# 04_MP_SIGNAL.net
KiCad netlist of a schematic drawn in Altium Designer
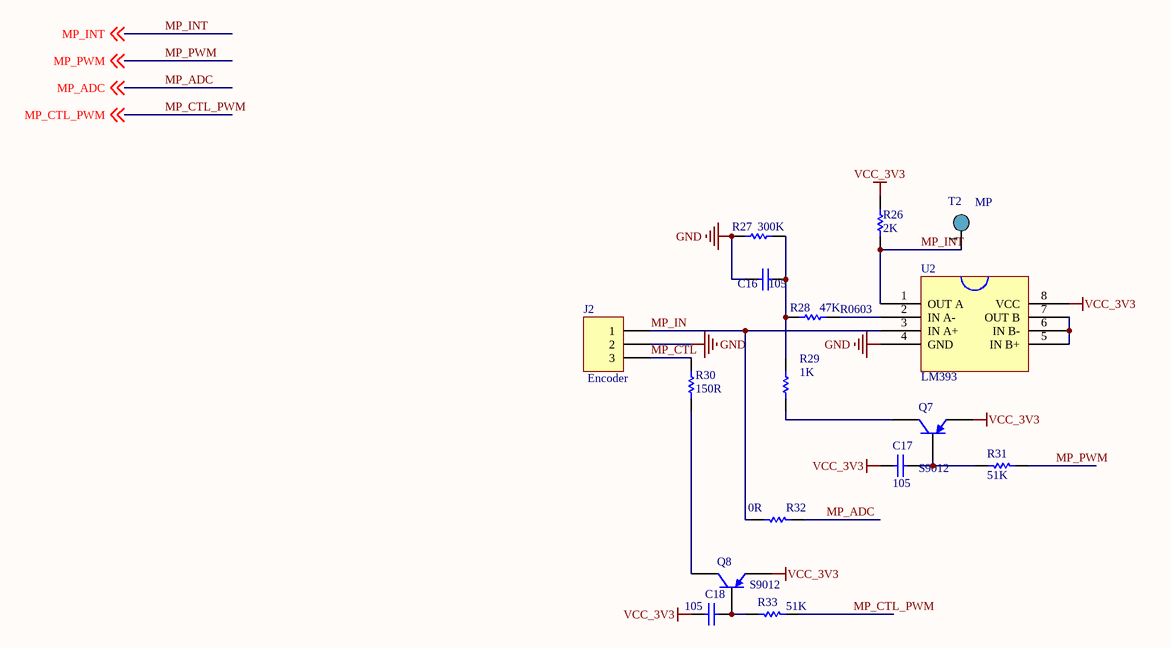
[diagram p0: 04 MP_SIGNAL.SchDoc]

(export (version "E")
  (design (tool "Eeschema 10.0.6"))
  (components
    (comp (ref "C16")
      (value "105")
      (footprint "R0603")
      (description "Capacitor")
      (fields
        (field (name "MANUFACTURER") "Generic Components")
        (field (name "PUBLISHER") "Altium Hobart Technology Centre")
      )
      (libsource (lib "") (part "Cap_1"))
    )
    (comp (ref "C17")
      (value "105")
      (footprint "C0603")
      (description "Capacitor")
      (fields
        (field (name "MANUFACTURER") "Generic Components")
        (field (name "PUBLISHER") "Altium Hobart Technology Centre")
      )
      (libsource (lib "") (part "Cap_1"))
    )
    (comp (ref "C18")
      (value "105")
      (footprint "C0603")
      (description "Capacitor")
      (fields
        (field (name "MANUFACTURER") "Generic Components")
        (field (name "PUBLISHER") "Altium Hobart Technology Centre")
      )
      (libsource (lib "Miscellaneous Devices") (part "Cap"))
    )
    (comp (ref "J2")
      (value "Encoder")
      (footprint "PH2.0*3")
      (description "Header, 3-Pin")
      (fields (field (name "MANUFACTURER") "Generic Components"))
      (libsource (lib "Miscellaneous Connectors") (part "Header 3"))
    )
    (comp (ref "Q7")
      (value "S9012")
      (footprint "PNP-SOT-23")
      (description "PNP General Purpose Amplifier")
      (fields (field (name "PUBLISHER") "Altium Limited"))
      (libsource (lib "Miscellaneous Devices") (part "2N3906"))
    )
    (comp (ref "Q8")
      (value "S9012")
      (footprint "PNP-SOT-23")
      (description "PNP General Purpose Amplifier")
      (fields (field (name "PUBLISHER") "Altium Limited"))
      (libsource (lib "Miscellaneous Devices") (part "2N3906"))
    )
    (comp (ref "R26")
      (value "2K")
      (footprint "R0603")
      (description "Resistor")
      (fields
        (field (name "MANUFACTURER") "Generic Components")
        (field (name "PUBLISHER") "Altium Hobart Technology Centre")
      )
      (libsource (lib "") (part "Res1_1"))
    )
    (comp (ref "R27")
      (value "300K")
      (footprint "R0603")
      (description "Resistor")
      (fields
        (field (name "MANUFACTURER") "Generic Components")
        (field (name "PUBLISHER") "Altium Hobart Technology Centre")
      )
      (libsource (lib "") (part "Res1_1"))
    )
    (comp (ref "R28")
      (value "47K")
      (footprint "R0603")
      (description "Resistor")
      (fields
        (field (name "MANUFACTURER") "Generic Components")
        (field (name "PUBLISHER") "Altium Hobart Technology Centre")
      )
      (libsource (lib "") (part "Res1_1"))
    )
    (comp (ref "R29")
      (value "1K")
      (footprint "R0603")
      (description "Resistor")
      (fields
        (field (name "MANUFACTURER") "Generic Components")
        (field (name "PUBLISHER") "Altium Hobart Technology Centre")
      )
      (libsource (lib "") (part "Res1_1"))
    )
    (comp (ref "R30")
      (value "150R")
      (footprint "R0603")
      (description "Resistor")
      (fields
        (field (name "MANUFACTURER") "Generic Components")
        (field (name "PUBLISHER") "Altium Hobart Technology Centre")
      )
      (libsource (lib "") (part "Res1_1"))
    )
    (comp (ref "R31")
      (value "51K")
      (footprint "R0603")
      (description "Resistor")
      (fields
        (field (name "MANUFACTURER") "Generic Components")
        (field (name "PUBLISHER") "Altium Hobart Technology Centre")
      )
      (libsource (lib "Miscellaneous Devices") (part "Res1"))
    )
    (comp (ref "R32")
      (value "0R")
      (footprint "R0603")
      (description "Resistor")
      (fields
        (field (name "MANUFACTURER") "Generic Components")
        (field (name "PUBLISHER") "Altium Hobart Technology Centre")
      )
      (libsource (lib "Miscellaneous Devices") (part "Res1"))
    )
    (comp (ref "R33")
      (value "51K")
      (footprint "R0603")
      (description "Resistor")
      (fields
        (field (name "MANUFACTURER") "Generic Components")
        (field (name "PUBLISHER") "Altium Hobart Technology Centre")
      )
      (libsource (lib "Miscellaneous Devices") (part "Res1"))
    )
    (comp (ref "T2") (value "MP") (footprint "测试点") (libsource (lib "CHQJ-SCH") (part "DIAN")))
    (comp (ref "U2")
      (value "LM393")
      (footprint "LM393")
      (libsource (lib "Integrated_Library") (part "LM393"))
    )
  )
  (nets
    (net (code "1") (name "/MP_CTL") (class "Default")
      (node (ref "J2") (pin "3") (pinfunction "3_3") (pintype "passive"))
      (node (ref "R30") (pin "2") (pinfunction "2_2") (pintype "passive"))
    )
    (net (code "2") (name "/MP_IN") (class "Default")
      (node (ref "J2") (pin "1") (pinfunction "1_1") (pintype "passive"))
      (node (ref "R32") (pin "2") (pinfunction "2_2") (pintype "passive"))
      (node (ref "U2") (pin "3") (pinfunction "IN_A+_3") (pintype "passive"))
    )
    (net (code "3") (name "GND") (class "Default")
      (node (ref "C16") (pin "1") (pinfunction "1_1") (pintype "passive"))
      (node (ref "J2") (pin "2") (pinfunction "2_2") (pintype "passive"))
      (node (ref "R27") (pin "1") (pinfunction "1_1") (pintype "passive"))
      (node (ref "U2") (pin "4") (pinfunction "GND_4") (pintype "passive"))
    )
    (net (code "4") (name "MP_ADC") (class "Default")
      (node (ref "R32") (pin "1") (pinfunction "1_1") (pintype "passive"))
    )
    (net (code "5") (name "MP_CTL_PWM") (class "Default")
      (node (ref "R33") (pin "1") (pinfunction "1_1") (pintype "passive"))
    )
    (net (code "6") (name "MP_INT") (class "Default")
      (node (ref "R26") (pin "2") (pinfunction "2_2") (pintype "passive"))
      (node (ref "T2") (pin "1") (pintype "passive"))
      (node (ref "U2") (pin "1") (pinfunction "OUT_A_1") (pintype "passive"))
    )
    (net (code "7") (name "MP_PWM") (class "Default")
      (node (ref "R31") (pin "1") (pinfunction "1_1") (pintype "passive"))
    )
    (net (code "8") (name "Net-(C16-Pad2)") (class "Default")
      (node (ref "C16") (pin "2") (pinfunction "2_2") (pintype "passive"))
      (node (ref "R27") (pin "2") (pinfunction "2_2") (pintype "passive"))
      (node (ref "R28") (pin "1") (pinfunction "1_1") (pintype "passive"))
      (node (ref "R29") (pin "1") (pinfunction "1_1") (pintype "passive"))
    )
    (net (code "9") (name "Net-(Q7-B)") (class "Default")
      (node (ref "C17") (pin "2") (pinfunction "2_2") (pintype "passive"))
      (node (ref "Q7") (pin "2") (pinfunction "B_2") (pintype "passive"))
      (node (ref "R31") (pin "2") (pinfunction "2_2") (pintype "passive"))
    )
    (net (code "10") (name "Net-(Q7-C)") (class "Default")
      (node (ref "Q7") (pin "3") (pinfunction "C_3") (pintype "passive"))
      (node (ref "R29") (pin "2") (pinfunction "2_2") (pintype "passive"))
    )
    (net (code "11") (name "Net-(Q8-B)") (class "Default")
      (node (ref "C18") (pin "1") (pinfunction "1_1") (pintype "passive"))
      (node (ref "Q8") (pin "2") (pinfunction "B_2") (pintype "passive"))
      (node (ref "R33") (pin "2") (pinfunction "2_2") (pintype "passive"))
    )
    (net (code "12") (name "Net-(Q8-C)") (class "Default")
      (node (ref "Q8") (pin "3") (pinfunction "C_3") (pintype "passive"))
      (node (ref "R30") (pin "1") (pinfunction "1_1") (pintype "passive"))
    )
    (net (code "13") (name "Net-(U2-IN_A-)") (class "Default")
      (node (ref "R28") (pin "2") (pinfunction "2_2") (pintype "passive"))
      (node (ref "U2") (pin "2") (pinfunction "IN_A-_2") (pintype "passive"))
    )
    (net (code "14") (name "Net-(U2-IN_B+)") (class "Default")
      (node (ref "U2") (pin "5") (pinfunction "IN_B+_5") (pintype "passive"))
      (node (ref "U2") (pin "6") (pinfunction "IN_B-_6") (pintype "passive"))
      (node (ref "U2") (pin "7") (pinfunction "OUT_B_7") (pintype "passive"))
    )
    (net (code "15") (name "VCC_3V3") (class "Default")
      (node (ref "C17") (pin "1") (pinfunction "1_1") (pintype "passive"))
      (node (ref "C18") (pin "2") (pinfunction "2_2") (pintype "passive"))
      (node (ref "Q7") (pin "1") (pinfunction "E_1") (pintype "passive"))
      (node (ref "Q8") (pin "1") (pinfunction "E_1") (pintype "passive"))
      (node (ref "R26") (pin "1") (pinfunction "1_1") (pintype "passive"))
      (node (ref "U2") (pin "8") (pinfunction "VCC_8") (pintype "passive"))
    )
  )
)
